# LED.net
KiCad netlist of a schematic drawn in Altium Designer
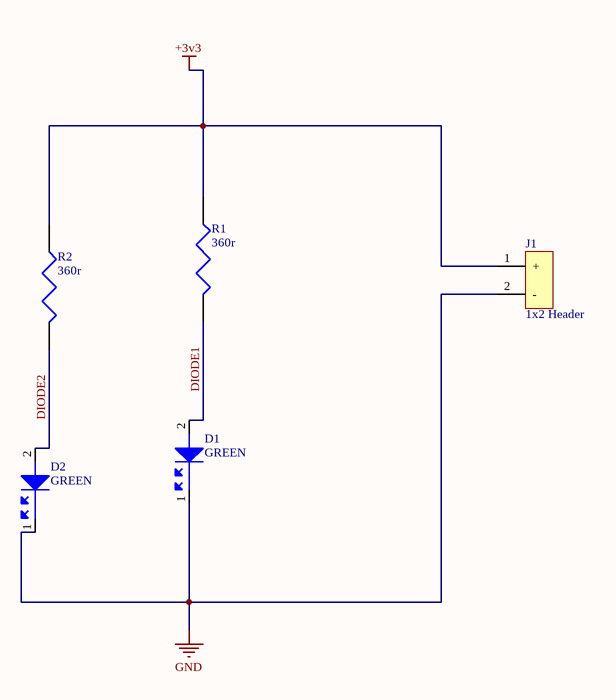
[diagram p0: LED.SchDoc]

(export (version "E")
  (design (tool "Eeschema 10.0.6"))
  (components
    (comp (ref "D1")
      (value "GREEN")
      (footprint "LED0603G")
      (description "LED GREEN ESS II SMD")
      (libsource (lib "LED_Schlib") (part "LNJ337W83RA"))
    )
    (comp (ref "D2")
      (value "GREEN")
      (footprint "LED0603G")
      (description "LED GREEN ESS II SMD")
      (libsource (lib "LED_Schlib") (part "LNJ337W83RA"))
    )
    (comp (ref "J1")
      (value "1x2 Header")
      (footprint "HDR1x2")
      (description "Conn Wire to Board HDR 2 POS 2.54mm Solder ST Thru-Hole Bag")
      (libsource (lib "LED_Schlib") (part "22-29-2021"))
    )
    (comp (ref "R1")
      (value "360r")
      (footprint "R0805")
      (description "RES SMD 360 OHM 1% 1/8W 0805")
      (fields (field (name "TOLERANCE") "1%"))
      (libsource (lib "LED_Schlib") (part "CRCW0805360RFKEA"))
    )
    (comp (ref "R2")
      (value "360r")
      (footprint "R0805")
      (description "RES SMD 360 OHM 1% 1/8W 0805")
      (fields (field (name "TOLERANCE") "1%"))
      (libsource (lib "LED_Schlib") (part "CRCW0805360RFKEA"))
    )
  )
  (nets
    (net (code "1") (name "+3v3") (class "Default")
      (node (ref "J1") (pin "1") (pinfunction "+_1") (pintype "passive"))
      (node (ref "R1") (pin "2") (pinfunction "2_2") (pintype "passive"))
      (node (ref "R2") (pin "2") (pinfunction "2_2") (pintype "passive"))
    )
    (net (code "2") (name "/DIODE1") (class "Default")
      (node (ref "D1") (pin "2") (pinfunction "2_2") (pintype "passive"))
      (node (ref "R1") (pin "1") (pinfunction "1_1") (pintype "passive"))
    )
    (net (code "3") (name "/DIODE2") (class "Default")
      (node (ref "D2") (pin "2") (pinfunction "2_2") (pintype "passive"))
      (node (ref "R2") (pin "1") (pinfunction "1_1") (pintype "passive"))
    )
    (net (code "4") (name "GND") (class "Default")
      (node (ref "D1") (pin "1") (pinfunction "1_1") (pintype "passive"))
      (node (ref "D2") (pin "1") (pinfunction "1_1") (pintype "passive"))
      (node (ref "J1") (pin "2") (pinfunction "-_2") (pintype "passive"))
    )
  )
)
